# NAKUJA_bmp_mpu_logic.net
KiCad netlist of a schematic drawn in EasyEDA
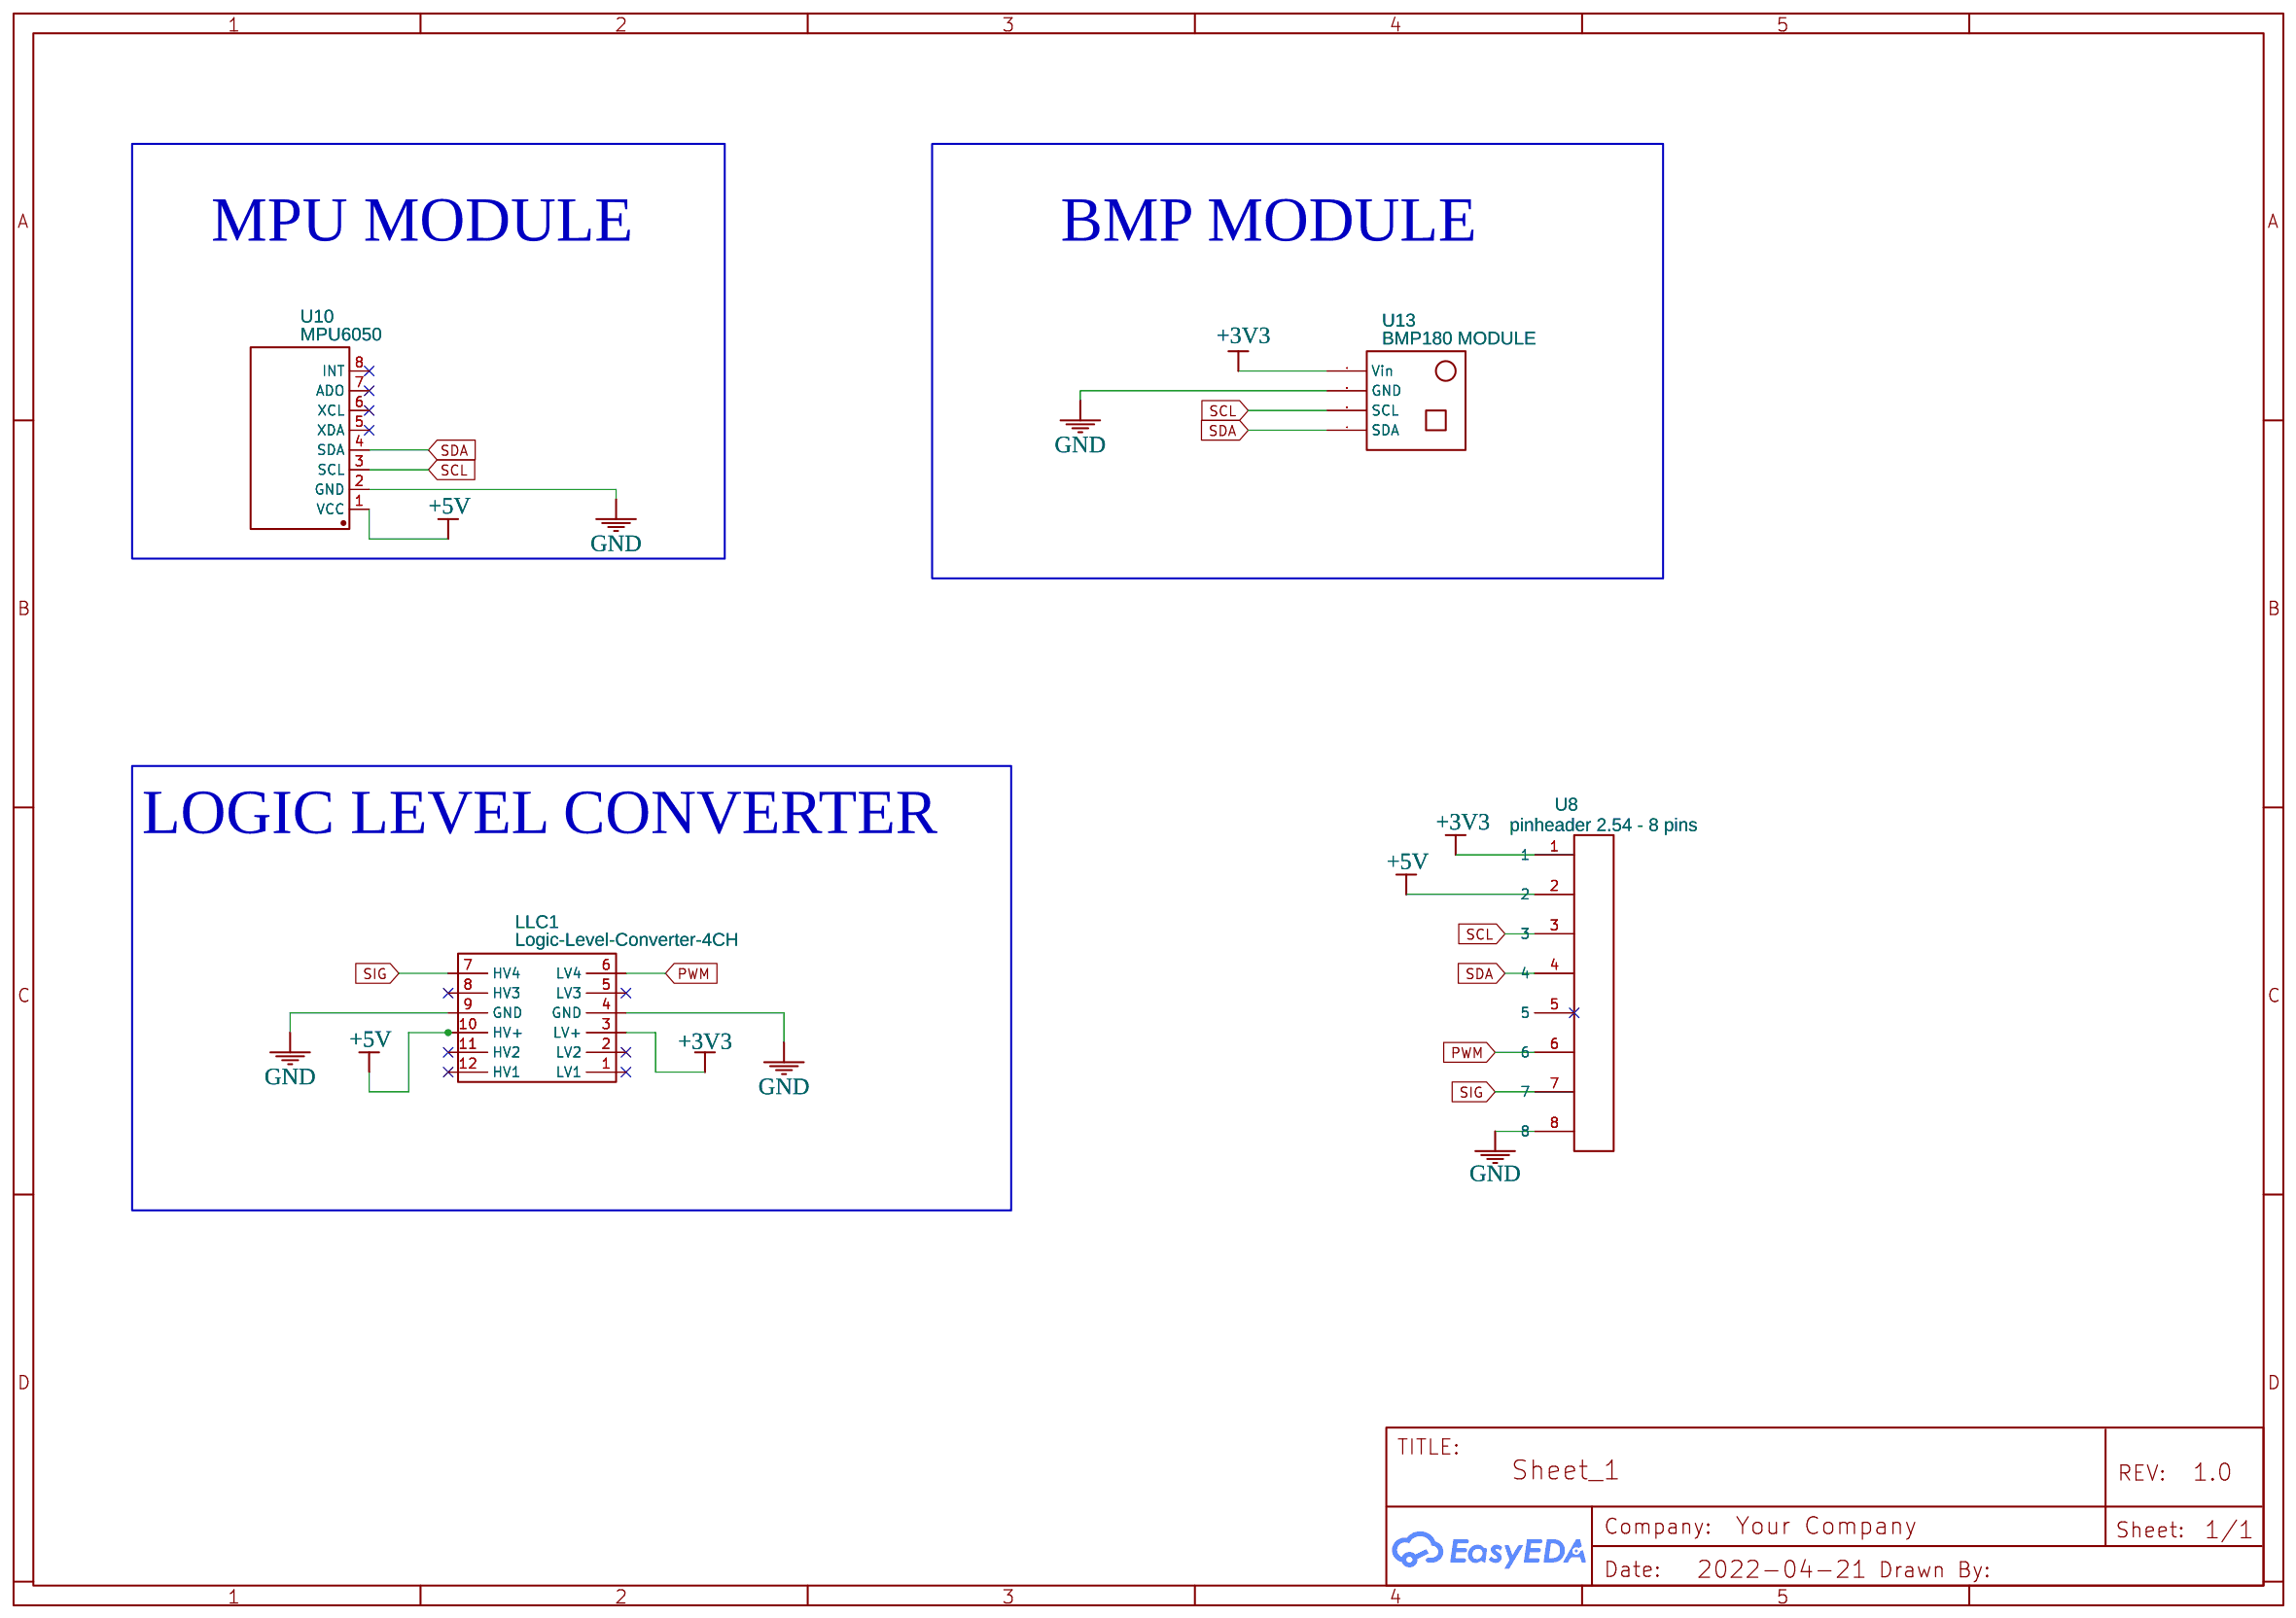
[diagram p0: schematic sheet]

(export (version "E")
  (design (tool "Eeschema 10.0.6"))
  (components
    (comp (ref "LLC1")
      (value "Logic-Level-Converter-4CH")
      (fields (field (name "BOM_Supplier Part") "50807"))
      (libsource (lib "") (part "Logic-Level-Converter-4CH"))
    )
    (comp (ref "U8") (value "pinheader 2.54 - 8 pins") (libsource (lib "") (part "pinheader 2.54 - 8 pins")))
    (comp (ref "U10")
      (value "MPU6050")
      (fields (field (name "BOM_Supplier Part") "GY521"))
      (libsource (lib "") (part "MPU6050"))
    )
    (comp (ref "U13")
      (value "BMP180 MODULE")
      (fields (field (name "BOM_Manufacturer Part") "BMP180 (HW-596)"))
      (libsource (lib "") (part "BMP180 MODULE"))
    )
  )
  (nets
    (net (code "1") (name "+3V3") (class "Default")
      (node (ref "LLC1") (pin "3") (pinfunction "LV+_3") (pintype "unspecified"))
      (node (ref "U13") (pin "1") (pinfunction "Vin_1") (pintype "unspecified"))
      (node (ref "U8") (pin "1") (pinfunction "1_1") (pintype "unspecified"))
    )
    (net (code "2") (name "+5V") (class "Default")
      (node (ref "LLC1") (pin "10") (pinfunction "HV+_10") (pintype "unspecified"))
      (node (ref "U10") (pin "1") (pinfunction "VCC_1") (pintype "unspecified"))
      (node (ref "U8") (pin "2") (pinfunction "2_2") (pintype "unspecified"))
    )
    (net (code "3") (name "GND") (class "Default")
      (node (ref "LLC1") (pin "4") (pinfunction "GND_4") (pintype "unspecified"))
      (node (ref "LLC1") (pin "9") (pinfunction "GND_9") (pintype "unspecified"))
      (node (ref "U10") (pin "2") (pinfunction "GND_2") (pintype "unspecified"))
      (node (ref "U13") (pin "2") (pinfunction "GND_2") (pintype "unspecified"))
      (node (ref "U8") (pin "8") (pinfunction "8_8") (pintype "unspecified"))
    )
    (net (code "4") (name "PWM") (class "Default")
      (node (ref "LLC1") (pin "6") (pinfunction "LV4_6") (pintype "unspecified"))
      (node (ref "U8") (pin "6") (pinfunction "6_6") (pintype "unspecified"))
    )
    (net (code "5") (name "SCL") (class "Default")
      (node (ref "U10") (pin "3") (pinfunction "SCL_3") (pintype "unspecified"))
      (node (ref "U13") (pin "3") (pinfunction "SCL_3") (pintype "unspecified"))
      (node (ref "U8") (pin "3") (pinfunction "3_3") (pintype "unspecified"))
    )
    (net (code "6") (name "SDA") (class "Default")
      (node (ref "U10") (pin "4") (pinfunction "SDA_4") (pintype "unspecified"))
      (node (ref "U13") (pin "4") (pinfunction "SDA_4") (pintype "unspecified"))
      (node (ref "U8") (pin "4") (pinfunction "4_4") (pintype "unspecified"))
    )
    (net (code "7") (name "SIG") (class "Default")
      (node (ref "LLC1") (pin "7") (pinfunction "HV4_7") (pintype "unspecified"))
      (node (ref "U8") (pin "7") (pinfunction "7_7") (pintype "unspecified"))
    )
    (net (code "8") (name "unconnected-(LLC1-HV1-Pad12)") (class "Default")
      (node (ref "LLC1") (pin "12") (pinfunction "HV1_12") (pintype "unspecified+no_connect"))
    )
    (net (code "9") (name "unconnected-(LLC1-HV2-Pad11)") (class "Default")
      (node (ref "LLC1") (pin "11") (pinfunction "HV2_11") (pintype "unspecified+no_connect"))
    )
    (net (code "10") (name "unconnected-(LLC1-HV3-Pad8)") (class "Default")
      (node (ref "LLC1") (pin "8") (pinfunction "HV3_8") (pintype "unspecified+no_connect"))
    )
    (net (code "11") (name "unconnected-(LLC1-LV1-Pad1)") (class "Default")
      (node (ref "LLC1") (pin "1") (pinfunction "LV1_1") (pintype "unspecified+no_connect"))
    )
    (net (code "12") (name "unconnected-(LLC1-LV2-Pad2)") (class "Default")
      (node (ref "LLC1") (pin "2") (pinfunction "LV2_2") (pintype "unspecified+no_connect"))
    )
    (net (code "13") (name "unconnected-(LLC1-LV3-Pad5)") (class "Default")
      (node (ref "LLC1") (pin "5") (pinfunction "LV3_5") (pintype "unspecified+no_connect"))
    )
    (net (code "14") (name "unconnected-(U8-Pad5)") (class "Default")
      (node (ref "U8") (pin "5") (pinfunction "5_5") (pintype "unspecified+no_connect"))
    )
    (net (code "15") (name "unconnected-(U10-ADO-Pad7)") (class "Default")
      (node (ref "U10") (pin "7") (pinfunction "ADO_7") (pintype "unspecified+no_connect"))
    )
    (net (code "16") (name "unconnected-(U10-INT-Pad8)") (class "Default")
      (node (ref "U10") (pin "8") (pinfunction "INT_8") (pintype "unspecified+no_connect"))
    )
    (net (code "17") (name "unconnected-(U10-XCL-Pad6)") (class "Default")
      (node (ref "U10") (pin "6") (pinfunction "XCL_6") (pintype "unspecified+no_connect"))
    )
    (net (code "18") (name "unconnected-(U10-XDA-Pad5)") (class "Default")
      (node (ref "U10") (pin "5") (pinfunction "XDA_5") (pintype "unspecified+no_connect"))
    )
  )
)
